# Quadrature_Mixers.net
KiCad netlist of a schematic drawn in Altium Designer
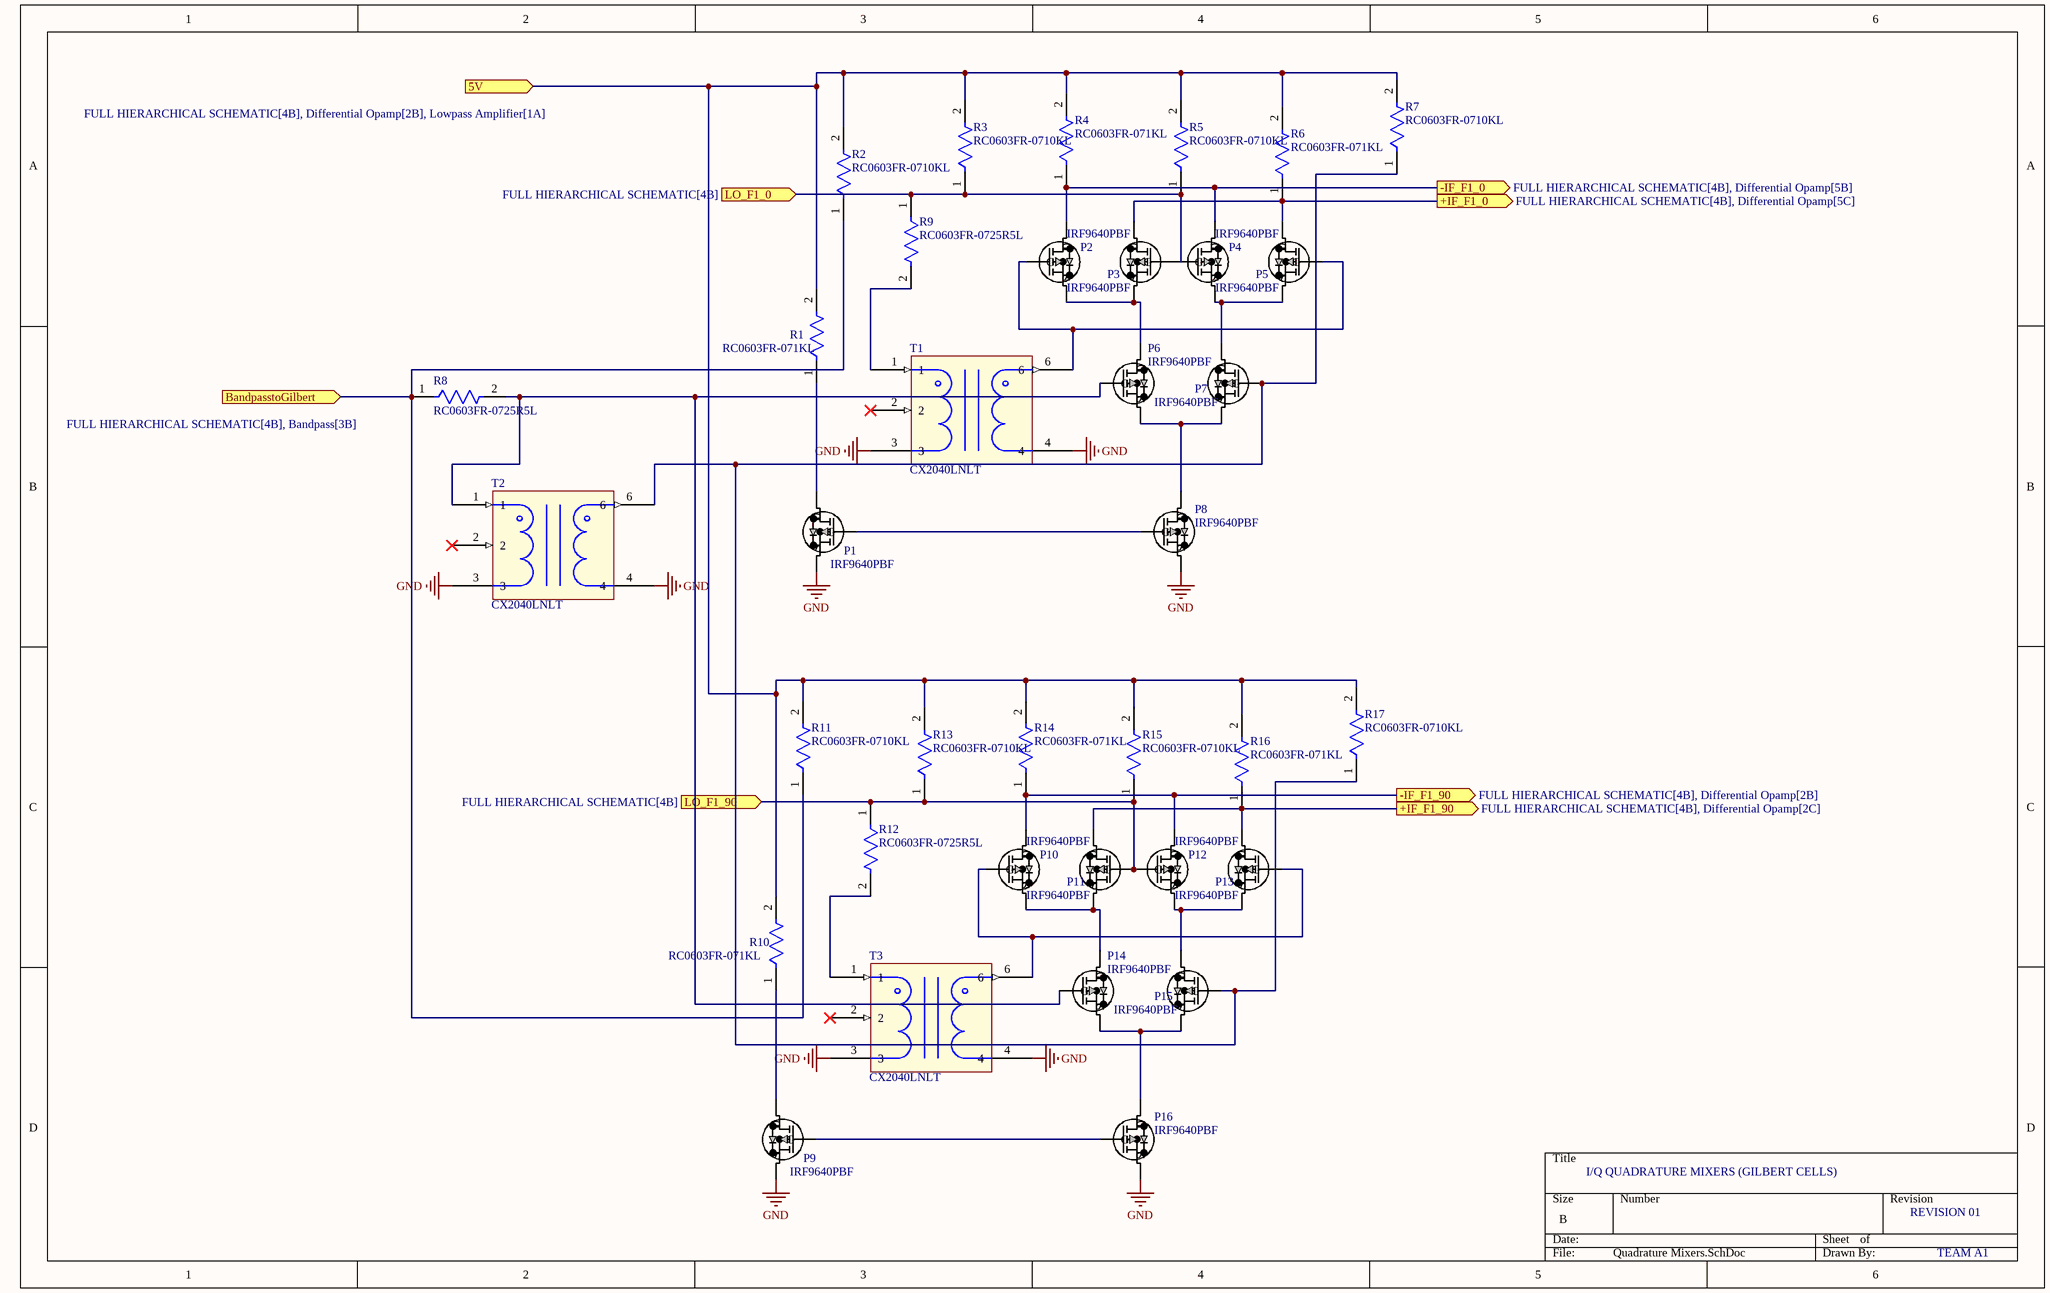
[diagram p0: Quadrature Mixers.SchDoc]

(export (version "E")
  (design (tool "Eeschema 10.0.6"))
  (components
    (comp (ref "P1")
      (value "IRF9640PBF")
      (footprint "TO220AB_VIS")
      (description "No Description Available")
      (libsource (lib "IRF9640PBF") (part "IRF9640PBF"))
    )
    (comp (ref "P2")
      (value "IRF9640PBF")
      (footprint "TO220AB_VIS")
      (description "No Description Available")
      (libsource (lib "IRF9640PBF") (part "IRF9640PBF"))
    )
    (comp (ref "P3")
      (value "IRF9640PBF")
      (footprint "TO220AB_VIS")
      (description "No Description Available")
      (libsource (lib "IRF9640PBF") (part "IRF9640PBF"))
    )
    (comp (ref "P4")
      (value "IRF9640PBF")
      (footprint "TO220AB_VIS")
      (description "No Description Available")
      (libsource (lib "IRF9640PBF") (part "IRF9640PBF"))
    )
    (comp (ref "P5")
      (value "IRF9640PBF")
      (footprint "TO220AB_VIS")
      (description "No Description Available")
      (libsource (lib "IRF9640PBF") (part "IRF9640PBF"))
    )
    (comp (ref "P6")
      (value "IRF9640PBF")
      (footprint "TO220AB_VIS")
      (description "No Description Available")
      (libsource (lib "IRF9640PBF") (part "IRF9640PBF"))
    )
    (comp (ref "P7")
      (value "IRF9640PBF")
      (footprint "TO220AB_VIS")
      (description "No Description Available")
      (libsource (lib "IRF9640PBF") (part "IRF9640PBF"))
    )
    (comp (ref "P8")
      (value "IRF9640PBF")
      (footprint "TO220AB_VIS")
      (description "No Description Available")
      (libsource (lib "IRF9640PBF") (part "IRF9640PBF"))
    )
    (comp (ref "P9")
      (value "IRF9640PBF")
      (footprint "TO220AB_VIS")
      (description "No Description Available")
      (libsource (lib "IRF9640PBF") (part "IRF9640PBF"))
    )
    (comp (ref "P10")
      (value "IRF9640PBF")
      (footprint "TO220AB_VIS")
      (description "No Description Available")
      (libsource (lib "IRF9640PBF") (part "IRF9640PBF"))
    )
    (comp (ref "P11")
      (value "IRF9640PBF")
      (footprint "TO220AB_VIS")
      (description "No Description Available")
      (libsource (lib "IRF9640PBF") (part "IRF9640PBF"))
    )
    (comp (ref "P12")
      (value "IRF9640PBF")
      (footprint "TO220AB_VIS")
      (description "No Description Available")
      (libsource (lib "IRF9640PBF") (part "IRF9640PBF"))
    )
    (comp (ref "P13")
      (value "IRF9640PBF")
      (footprint "TO220AB_VIS")
      (description "No Description Available")
      (libsource (lib "IRF9640PBF") (part "IRF9640PBF"))
    )
    (comp (ref "P14")
      (value "IRF9640PBF")
      (footprint "TO220AB_VIS")
      (description "No Description Available")
      (libsource (lib "IRF9640PBF") (part "IRF9640PBF"))
    )
    (comp (ref "P15")
      (value "IRF9640PBF")
      (footprint "TO220AB_VIS")
      (description "No Description Available")
      (libsource (lib "IRF9640PBF") (part "IRF9640PBF"))
    )
    (comp (ref "P16")
      (value "IRF9640PBF")
      (footprint "TO220AB_VIS")
      (description "No Description Available")
      (libsource (lib "IRF9640PBF") (part "IRF9640PBF"))
    )
    (comp (ref "R1")
      (value "RC0603FR-071KL")
      (footprint "FP-RC0603-0_55-IPC_C")
      (description "RES 1K OHM 1% 1/10W 0603")
      (fields (field (name "TOLERANCE") "1%"))
      (libsource (lib "Altium Content Vault") (part "1029c3af85768c4190bb7ad29bc67b5"))
    )
    (comp (ref "R2")
      (value "RC0603FR-0710KL")
      (footprint "FP-RC0603-0_55-IPC_C")
      (description "RES 10K OHM 1% 1/10W 0603")
      (fields (field (name "TOLERANCE") "1%"))
      (libsource (lib "Altium Content Vault") (part "1029c3af85768c4190bb7ad29bc67b5"))
    )
    (comp (ref "R3")
      (value "RC0603FR-0710KL")
      (footprint "FP-RC0603-0_55-IPC_C")
      (description "RES 10K OHM 1% 1/10W 0603")
      (fields (field (name "TOLERANCE") "1%"))
      (libsource (lib "Altium Content Vault") (part "1029c3af85768c4190bb7ad29bc67b5"))
    )
    (comp (ref "R4")
      (value "RC0603FR-071KL")
      (footprint "FP-RC0603-0_55-IPC_C")
      (description "RES 1K OHM 1% 1/10W 0603")
      (fields (field (name "TOLERANCE") "1%"))
      (libsource (lib "Altium Content Vault") (part "1029c3af85768c4190bb7ad29bc67b5"))
    )
    (comp (ref "R5")
      (value "RC0603FR-0710KL")
      (footprint "FP-RC0603-0_55-IPC_C")
      (description "RES 10K OHM 1% 1/10W 0603")
      (fields (field (name "TOLERANCE") "1%"))
      (libsource (lib "Altium Content Vault") (part "1029c3af85768c4190bb7ad29bc67b5"))
    )
    (comp (ref "R6")
      (value "RC0603FR-071KL")
      (footprint "FP-RC0603-0_55-IPC_C")
      (description "RES 1K OHM 1% 1/10W 0603")
      (fields (field (name "TOLERANCE") "1%"))
      (libsource (lib "Altium Content Vault") (part "1029c3af85768c4190bb7ad29bc67b5"))
    )
    (comp (ref "R7")
      (value "RC0603FR-0710KL")
      (footprint "FP-RC0603-0_55-IPC_C")
      (description "RES 10K OHM 1% 1/10W 0603")
      (fields (field (name "TOLERANCE") "1%"))
      (libsource (lib "Altium Content Vault") (part "1029c3af85768c4190bb7ad29bc67b5"))
    )
    (comp (ref "R8")
      (value "RC0603FR-0725R5L")
      (footprint "FP-RC0603-0_55-IPC_C")
      (description "RES 1K OHM 1% 1/10W 0603")
      (fields (field (name "TOLERANCE") "1%"))
      (libsource (lib "Altium Content Vault") (part "1029c3af85768c4190bb7ad29bc67b5"))
    )
    (comp (ref "R9")
      (value "RC0603FR-0725R5L")
      (footprint "FP-RC0603-0_55-IPC_C")
      (description "RES 1K OHM 1% 1/10W 0603")
      (fields (field (name "TOLERANCE") "1%"))
      (libsource (lib "Altium Content Vault") (part "1029c3af85768c4190bb7ad29bc67b5"))
    )
    (comp (ref "R10")
      (value "RC0603FR-071KL")
      (footprint "FP-RC0603-0_55-IPC_C")
      (description "RES 1K OHM 1% 1/10W 0603")
      (fields (field (name "TOLERANCE") "1%"))
      (libsource (lib "Altium Content Vault") (part "1029c3af85768c4190bb7ad29bc67b5"))
    )
    (comp (ref "R11")
      (value "RC0603FR-0710KL")
      (footprint "FP-RC0603-0_55-IPC_C")
      (description "RES 10K OHM 1% 1/10W 0603")
      (fields (field (name "TOLERANCE") "1%"))
      (libsource (lib "Altium Content Vault") (part "1029c3af85768c4190bb7ad29bc67b5"))
    )
    (comp (ref "R12")
      (value "RC0603FR-0725R5L")
      (footprint "FP-RC0603-0_55-IPC_C")
      (description "RES 1K OHM 1% 1/10W 0603")
      (fields (field (name "TOLERANCE") "1%"))
      (libsource (lib "Altium Content Vault") (part "1029c3af85768c4190bb7ad29bc67b5"))
    )
    (comp (ref "R13")
      (value "RC0603FR-0710KL")
      (footprint "FP-RC0603-0_55-IPC_C")
      (description "RES 10K OHM 1% 1/10W 0603")
      (fields (field (name "TOLERANCE") "1%"))
      (libsource (lib "Altium Content Vault") (part "1029c3af85768c4190bb7ad29bc67b5"))
    )
    (comp (ref "R14")
      (value "RC0603FR-071KL")
      (footprint "FP-RC0603-0_55-IPC_C")
      (description "RES 1K OHM 1% 1/10W 0603")
      (fields (field (name "TOLERANCE") "1%"))
      (libsource (lib "Altium Content Vault") (part "1029c3af85768c4190bb7ad29bc67b5"))
    )
    (comp (ref "R15")
      (value "RC0603FR-0710KL")
      (footprint "FP-RC0603-0_55-IPC_C")
      (description "RES 10K OHM 1% 1/10W 0603")
      (fields (field (name "TOLERANCE") "1%"))
      (libsource (lib "Altium Content Vault") (part "1029c3af85768c4190bb7ad29bc67b5"))
    )
    (comp (ref "R16")
      (value "RC0603FR-071KL")
      (footprint "FP-RC0603-0_55-IPC_C")
      (description "RES 1K OHM 1% 1/10W 0603")
      (fields (field (name "TOLERANCE") "1%"))
      (libsource (lib "Altium Content Vault") (part "1029c3af85768c4190bb7ad29bc67b5"))
    )
    (comp (ref "R17")
      (value "RC0603FR-0710KL")
      (footprint "FP-RC0603-0_55-IPC_C")
      (description "RES 10K OHM 1% 1/10W 0603")
      (fields (field (name "TOLERANCE") "1%"))
      (libsource (lib "Altium Content Vault") (part "1029c3af85768c4190bb7ad29bc67b5"))
    )
    (comp (ref "T1")
      (value "CX2040LNLT")
      (footprint "CX2040LNLT")
      (description "BALUN 1MHZ-500MHZ 75/75 5SMD MOD")
      (fields (field (name "MANUFACTURER") "Pulse Electronics"))
      (libsource (lib "CX2040LNLT_component") (part "CX2040LNLT"))
    )
    (comp (ref "T2")
      (value "CX2040LNLT")
      (footprint "CX2040LNLT")
      (description "BALUN 1MHZ-500MHZ 75/75 5SMD MOD")
      (fields (field (name "MANUFACTURER") "Pulse Electronics"))
      (libsource (lib "CX2040LNLT_component") (part "CX2040LNLT"))
    )
    (comp (ref "T3")
      (value "CX2040LNLT")
      (footprint "CX2040LNLT")
      (description "BALUN 1MHZ-500MHZ 75/75 5SMD MOD")
      (fields (field (name "MANUFACTURER") "Pulse Electronics"))
      (libsource (lib "CX2040LNLT_component") (part "CX2040LNLT"))
    )
  )
  (nets
    (net (code "1") (name "/+IF_F1_0") (class "Default")
      (node (ref "P3") (pin "2") (pinfunction "D_2") (pintype "passive"))
      (node (ref "P5") (pin "2") (pinfunction "D_2") (pintype "passive"))
      (node (ref "R6") (pin "1") (pinfunction "1_1") (pintype "passive"))
    )
    (net (code "2") (name "/+IF_F1_90") (class "Default")
      (node (ref "P11") (pin "2") (pinfunction "D_2") (pintype "passive"))
      (node (ref "P13") (pin "2") (pinfunction "D_2") (pintype "passive"))
      (node (ref "R16") (pin "1") (pinfunction "1_1") (pintype "passive"))
    )
    (net (code "3") (name "/-IF_F1_0") (class "Default")
      (node (ref "P2") (pin "2") (pinfunction "D_2") (pintype "passive"))
      (node (ref "P4") (pin "2") (pinfunction "D_2") (pintype "passive"))
      (node (ref "R4") (pin "1") (pinfunction "1_1") (pintype "passive"))
    )
    (net (code "4") (name "/-IF_F1_90") (class "Default")
      (node (ref "P10") (pin "2") (pinfunction "D_2") (pintype "passive"))
      (node (ref "P12") (pin "2") (pinfunction "D_2") (pintype "passive"))
      (node (ref "R14") (pin "1") (pinfunction "1_1") (pintype "passive"))
    )
    (net (code "5") (name "/5V") (class "Default")
      (node (ref "R1") (pin "2") (pinfunction "2_2") (pintype "passive"))
      (node (ref "R10") (pin "2") (pinfunction "2_2") (pintype "passive"))
      (node (ref "R11") (pin "2") (pinfunction "2_2") (pintype "passive"))
      (node (ref "R13") (pin "2") (pinfunction "2_2") (pintype "passive"))
      (node (ref "R14") (pin "2") (pinfunction "2_2") (pintype "passive"))
      (node (ref "R15") (pin "2") (pinfunction "2_2") (pintype "passive"))
      (node (ref "R16") (pin "2") (pinfunction "2_2") (pintype "passive"))
      (node (ref "R17") (pin "2") (pinfunction "2_2") (pintype "passive"))
      (node (ref "R2") (pin "2") (pinfunction "2_2") (pintype "passive"))
      (node (ref "R3") (pin "2") (pinfunction "2_2") (pintype "passive"))
      (node (ref "R4") (pin "2") (pinfunction "2_2") (pintype "passive"))
      (node (ref "R5") (pin "2") (pinfunction "2_2") (pintype "passive"))
      (node (ref "R6") (pin "2") (pinfunction "2_2") (pintype "passive"))
      (node (ref "R7") (pin "2") (pinfunction "2_2") (pintype "passive"))
    )
    (net (code "6") (name "/BandpasstoGilbert") (class "Default")
      (node (ref "R11") (pin "1") (pinfunction "1_1") (pintype "passive"))
      (node (ref "R2") (pin "1") (pinfunction "1_1") (pintype "passive"))
      (node (ref "R8") (pin "1") (pinfunction "1_1") (pintype "passive"))
    )
    (net (code "7") (name "/LO_F1_0") (class "Default")
      (node (ref "R3") (pin "1") (pinfunction "1_1") (pintype "passive"))
      (node (ref "R5") (pin "1") (pinfunction "1_1") (pintype "passive"))
      (node (ref "R9") (pin "1") (pinfunction "1_1") (pintype "passive"))
    )
    (net (code "8") (name "/LO_F1_90") (class "Default")
      (node (ref "P11") (pin "1") (pinfunction "G_1") (pintype "passive"))
      (node (ref "P12") (pin "1") (pinfunction "G_1") (pintype "passive"))
      (node (ref "R12") (pin "1") (pinfunction "1_1") (pintype "passive"))
      (node (ref "R13") (pin "1") (pinfunction "1_1") (pintype "passive"))
      (node (ref "R15") (pin "1") (pinfunction "1_1") (pintype "passive"))
    )
    (net (code "9") (name "GND") (class "Default")
      (node (ref "P1") (pin "3") (pinfunction "S_3") (pintype "passive"))
      (node (ref "P16") (pin "3") (pinfunction "S_3") (pintype "passive"))
      (node (ref "P8") (pin "3") (pinfunction "S_3") (pintype "passive"))
      (node (ref "P9") (pin "3") (pinfunction "S_3") (pintype "passive"))
      (node (ref "T1") (pin "3") (pinfunction "3_3") (pintype "passive"))
      (node (ref "T1") (pin "4") (pinfunction "4_4") (pintype "passive"))
      (node (ref "T2") (pin "3") (pinfunction "3_3") (pintype "passive"))
      (node (ref "T2") (pin "4") (pinfunction "4_4") (pintype "passive"))
      (node (ref "T3") (pin "3") (pinfunction "3_3") (pintype "passive"))
      (node (ref "T3") (pin "4") (pinfunction "4_4") (pintype "passive"))
    )
    (net (code "10") (name "Net-(P1-D)") (class "Default")
      (node (ref "P1") (pin "2") (pinfunction "D_2") (pintype "passive"))
      (node (ref "R1") (pin "1") (pinfunction "1_1") (pintype "passive"))
    )
    (net (code "11") (name "Net-(P1-G)") (class "Default")
      (node (ref "P1") (pin "1") (pinfunction "G_1") (pintype "passive"))
      (node (ref "P8") (pin "1") (pinfunction "G_1") (pintype "passive"))
    )
    (net (code "12") (name "Net-(P2-G)") (class "Default")
      (node (ref "P2") (pin "1") (pinfunction "G_1") (pintype "passive"))
      (node (ref "P5") (pin "1") (pinfunction "G_1") (pintype "passive"))
      (node (ref "T1") (pin "6") (pinfunction "6_6") (pintype "output"))
    )
    (net (code "13") (name "Net-(P2-S)") (class "Default")
      (node (ref "P2") (pin "3") (pinfunction "S_3") (pintype "passive"))
      (node (ref "P3") (pin "3") (pinfunction "S_3") (pintype "passive"))
      (node (ref "P6") (pin "2") (pinfunction "D_2") (pintype "passive"))
    )
    (net (code "14") (name "Net-(P3-G)") (class "Default")
      (node (ref "P3") (pin "1") (pinfunction "G_1") (pintype "passive"))
      (node (ref "P4") (pin "1") (pinfunction "G_1") (pintype "passive"))
    )
    (net (code "15") (name "Net-(P4-S)") (class "Default")
      (node (ref "P4") (pin "3") (pinfunction "S_3") (pintype "passive"))
      (node (ref "P5") (pin "3") (pinfunction "S_3") (pintype "passive"))
      (node (ref "P7") (pin "2") (pinfunction "D_2") (pintype "passive"))
    )
    (net (code "16") (name "Net-(P6-S)") (class "Default")
      (node (ref "P6") (pin "3") (pinfunction "S_3") (pintype "passive"))
      (node (ref "P7") (pin "3") (pinfunction "S_3") (pintype "passive"))
      (node (ref "P8") (pin "2") (pinfunction "D_2") (pintype "passive"))
    )
    (net (code "17") (name "Net-(P9-D)") (class "Default")
      (node (ref "P9") (pin "2") (pinfunction "D_2") (pintype "passive"))
      (node (ref "R10") (pin "1") (pinfunction "1_1") (pintype "passive"))
    )
    (net (code "18") (name "Net-(P10-G)") (class "Default")
      (node (ref "P10") (pin "1") (pinfunction "G_1") (pintype "passive"))
      (node (ref "P13") (pin "1") (pinfunction "G_1") (pintype "passive"))
      (node (ref "T3") (pin "6") (pinfunction "6_6") (pintype "output"))
    )
    (net (code "19") (name "Net-(P10-S)") (class "Default")
      (node (ref "P10") (pin "3") (pinfunction "S_3") (pintype "passive"))
      (node (ref "P11") (pin "3") (pinfunction "S_3") (pintype "passive"))
      (node (ref "P14") (pin "2") (pinfunction "D_2") (pintype "passive"))
    )
    (net (code "20") (name "Net-(P12-S)") (class "Default")
      (node (ref "P12") (pin "3") (pinfunction "S_3") (pintype "passive"))
      (node (ref "P13") (pin "3") (pinfunction "S_3") (pintype "passive"))
      (node (ref "P15") (pin "2") (pinfunction "D_2") (pintype "passive"))
    )
    (net (code "21") (name "Net-(P14-G)") (class "Default")
      (node (ref "P14") (pin "1") (pinfunction "G_1") (pintype "passive"))
      (node (ref "P6") (pin "1") (pinfunction "G_1") (pintype "passive"))
      (node (ref "R8") (pin "2") (pinfunction "2_2") (pintype "passive"))
      (node (ref "T2") (pin "1") (pinfunction "1_1") (pintype "input"))
    )
    (net (code "22") (name "Net-(P14-S)") (class "Default")
      (node (ref "P14") (pin "3") (pinfunction "S_3") (pintype "passive"))
      (node (ref "P15") (pin "3") (pinfunction "S_3") (pintype "passive"))
      (node (ref "P16") (pin "2") (pinfunction "D_2") (pintype "passive"))
    )
    (net (code "23") (name "Net-(P15-G)") (class "Default")
      (node (ref "P15") (pin "1") (pinfunction "G_1") (pintype "passive"))
      (node (ref "P7") (pin "1") (pinfunction "G_1") (pintype "passive"))
      (node (ref "R17") (pin "1") (pinfunction "1_1") (pintype "passive"))
      (node (ref "R7") (pin "1") (pinfunction "1_1") (pintype "passive"))
      (node (ref "T2") (pin "6") (pinfunction "6_6") (pintype "output"))
    )
    (net (code "24") (name "Net-(P16-G)") (class "Default")
      (node (ref "P16") (pin "1") (pinfunction "G_1") (pintype "passive"))
      (node (ref "P9") (pin "1") (pinfunction "G_1") (pintype "passive"))
    )
    (net (code "25") (name "Net-(R9-Pad2)") (class "Default")
      (node (ref "R9") (pin "2") (pinfunction "2_2") (pintype "passive"))
      (node (ref "T1") (pin "1") (pinfunction "1_1") (pintype "input"))
    )
    (net (code "26") (name "Net-(R12-Pad2)") (class "Default")
      (node (ref "R12") (pin "2") (pinfunction "2_2") (pintype "passive"))
      (node (ref "T3") (pin "1") (pinfunction "1_1") (pintype "input"))
    )
    (net (code "27") (name "unconnected-(T1-Pad2)") (class "Default")
      (node (ref "T1") (pin "2") (pinfunction "2_2") (pintype "input+no_connect"))
    )
    (net (code "28") (name "unconnected-(T2-Pad2)") (class "Default")
      (node (ref "T2") (pin "2") (pinfunction "2_2") (pintype "input+no_connect"))
    )
    (net (code "29") (name "unconnected-(T3-Pad2)") (class "Default")
      (node (ref "T3") (pin "2") (pinfunction "2_2") (pintype "input+no_connect"))
    )
  )
)
